# RJ11BMP180_SiHyg.net
KiCad netlist of a schematic drawn in EAGLE
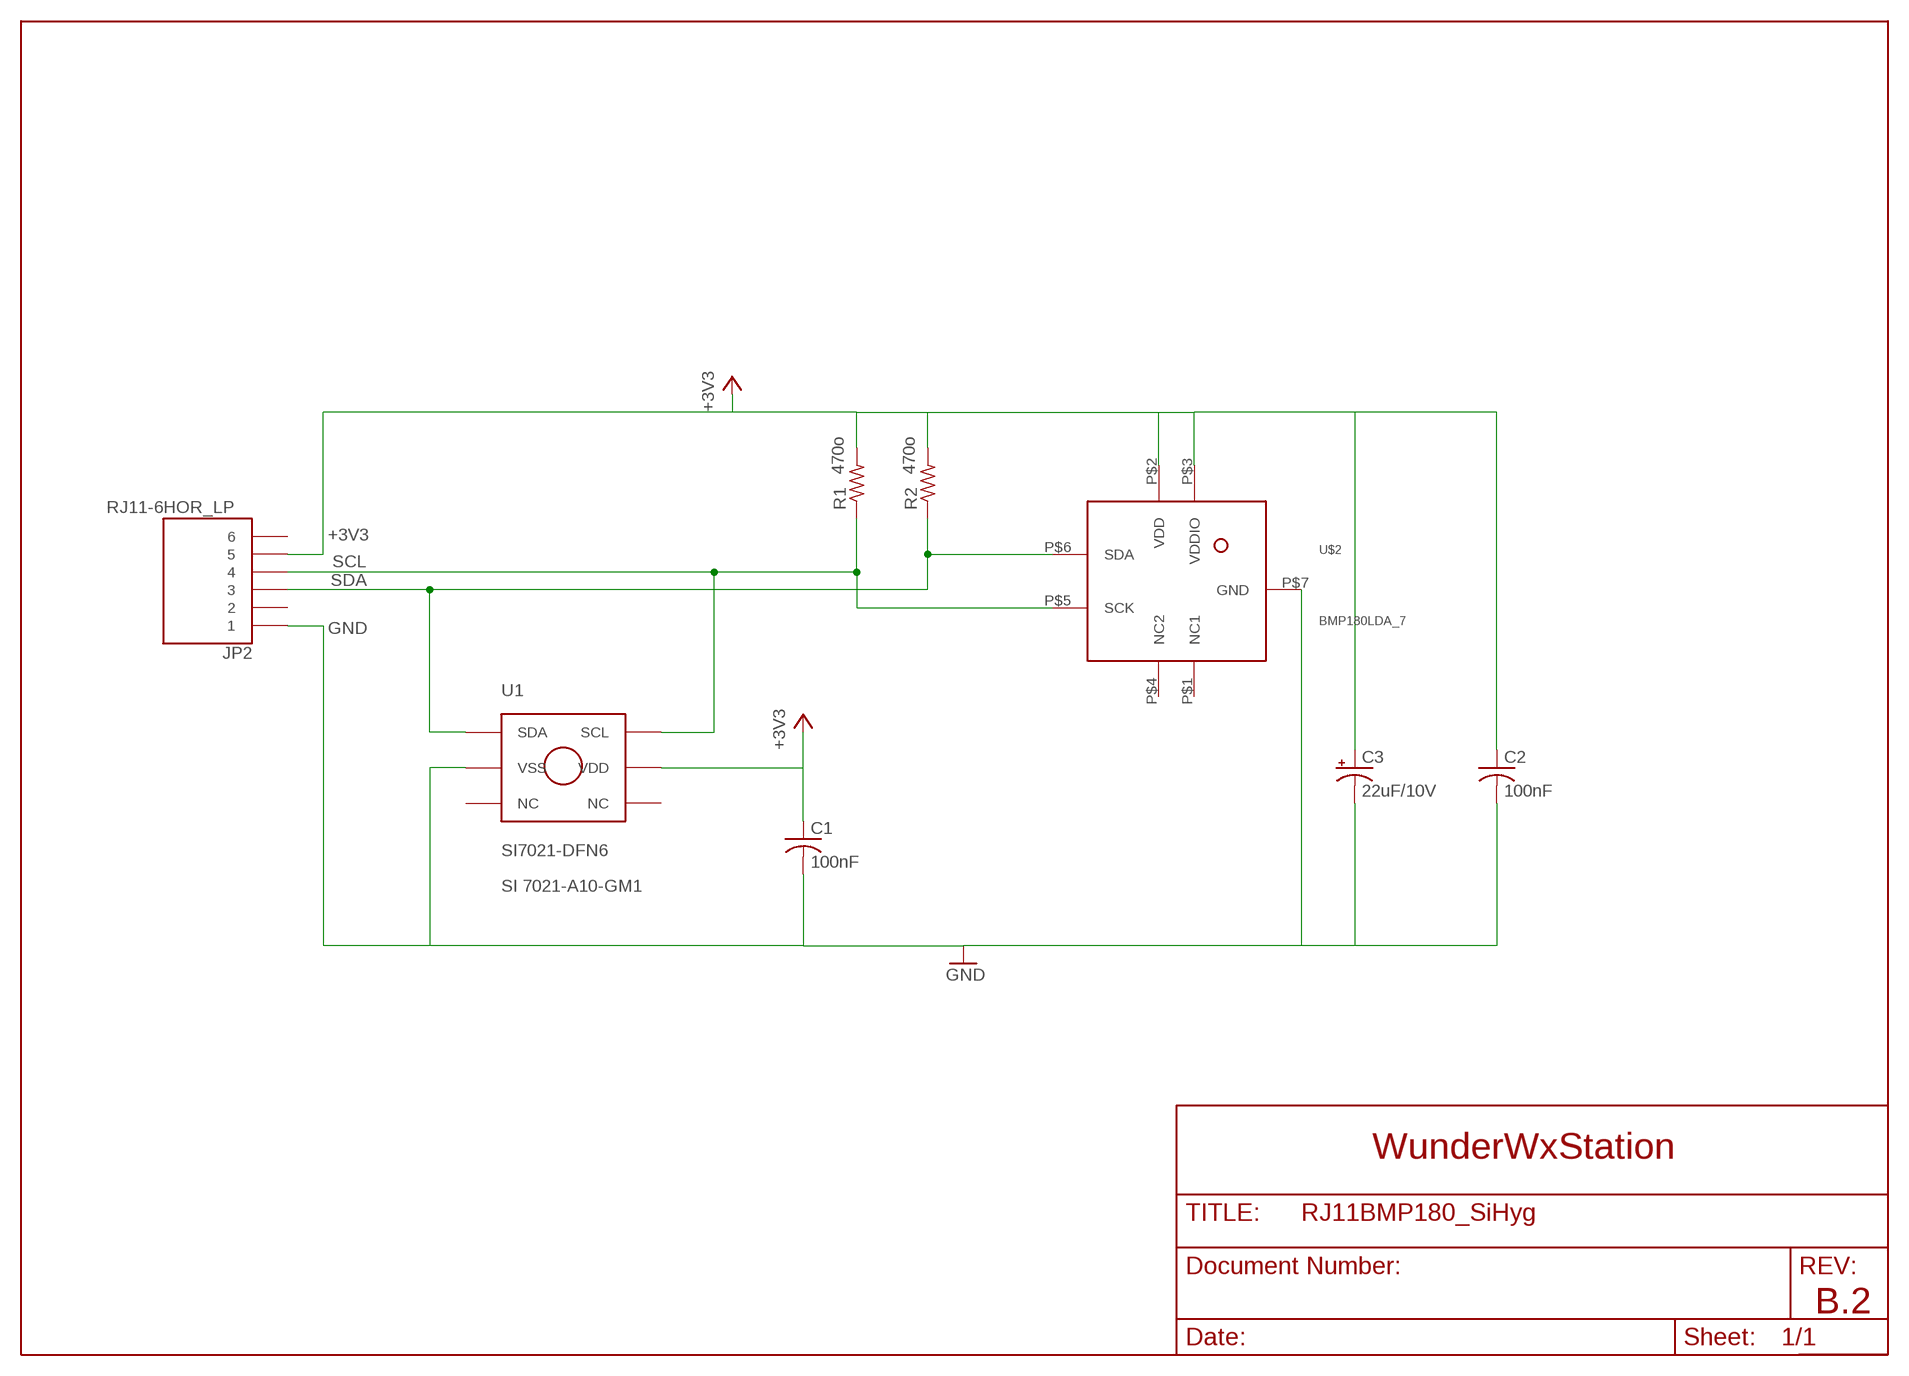
[diagram p0: schematic, sheet 1]

(export (version "E")
  (design (tool "Eeschema 10.0.6"))
  (components
    (comp (ref "C1")
      (value "100nF")
      (footprint "eagle-import:C0805K")
      (libsource (lib "eagle-import") (part "C-USC0805K"))
    )
    (comp (ref "C2")
      (value "100nF")
      (footprint "eagle-import:C0805K")
      (libsource (lib "eagle-import") (part "C-USC0805K"))
    )
    (comp (ref "C3")
      (value "22uF/10V")
      (footprint "eagle-import:SMC_B")
      (libsource (lib "eagle-import") (part "CPOL-USSMCB"))
    )
    (comp (ref "JP2")
      (value "RJ11-6HOR_LP")
      (footprint "eagle-import:RJ11_HOR_LP")
      (libsource (lib "eagle-import") (part "RJ11-6HOR_LP"))
    )
    (comp (ref "R1")
      (value "470o")
      (footprint "eagle-import:R0603")
      (libsource (lib "eagle-import") (part "R-US_R0603"))
    )
    (comp (ref "R2")
      (value "470o")
      (footprint "eagle-import:R0603")
      (libsource (lib "eagle-import") (part "R-US_R0603"))
    )
    (comp (ref "U$2")
      (value "BMP180LDA_7")
      (footprint "eagle-import:LGA_7")
      (libsource (lib "eagle-import") (part "BMP180LDA_7"))
    )
    (comp (ref "U1")
      (value "SI7021-DFN6")
      (footprint "eagle-import:DFN-6_SILABS")
      (libsource (lib "eagle-import") (part "SI7021-DFN6"))
    )
  )
  (nets
    (net (code "1") (name "+3V3") (class "Default")
      (node (ref "C1") (pin "1") (pinfunction "1_1") (pintype "passive"))
      (node (ref "C2") (pin "1") (pinfunction "1_1") (pintype "passive"))
      (node (ref "C3") (pin "+") (pinfunction "+_+") (pintype "passive"))
      (node (ref "JP2") (pin "P$5") (pinfunction "5_P$5") (pintype "bidirectional"))
      (node (ref "R1") (pin "2") (pinfunction "2_2") (pintype "passive"))
      (node (ref "R2") (pin "2") (pinfunction "2_2") (pintype "passive"))
      (node (ref "U$2") (pin "P$2") (pinfunction "VDD_P$2") (pintype "power_in"))
      (node (ref "U$2") (pin "P$3") (pinfunction "VDDIO_P$3") (pintype "power_in"))
      (node (ref "U1") (pin "P$5") (pinfunction "VDD_P$5") (pintype "power_in"))
    )
    (net (code "2") (name "/SCL") (class "Default")
      (node (ref "JP2") (pin "P$4") (pinfunction "4_P$4") (pintype "bidirectional"))
      (node (ref "R1") (pin "1") (pinfunction "1_1") (pintype "passive"))
      (node (ref "U$2") (pin "P$5") (pinfunction "SCK_P$5") (pintype "input"))
      (node (ref "U1") (pin "P$6") (pinfunction "SCL_P$6") (pintype "bidirectional"))
    )
    (net (code "3") (name "/SDA") (class "Default")
      (node (ref "JP2") (pin "P$3") (pinfunction "3_P$3") (pintype "bidirectional"))
      (node (ref "R2") (pin "1") (pinfunction "1_1") (pintype "passive"))
      (node (ref "U$2") (pin "P$6") (pinfunction "SDA_P$6") (pintype "bidirectional"))
      (node (ref "U1") (pin "P$1") (pinfunction "SDA_P$1") (pintype "bidirectional"))
    )
    (net (code "4") (name "GND") (class "Default")
      (node (ref "C1") (pin "2") (pinfunction "2_2") (pintype "passive"))
      (node (ref "C2") (pin "2") (pinfunction "2_2") (pintype "passive"))
      (node (ref "C3") (pin "-") (pinfunction "-_-") (pintype "passive"))
      (node (ref "JP2") (pin "P$1") (pinfunction "1_P$1") (pintype "bidirectional"))
      (node (ref "U$2") (pin "P$7") (pinfunction "GND_P$7") (pintype "power_in"))
      (node (ref "U1") (pin "P$2") (pinfunction "VSS_P$2") (pintype "power_in"))
    )
    (net (code "5") (name "unconnected-(JP2-2-PadP$2)") (class "Default")
      (node (ref "JP2") (pin "P$2") (pinfunction "2_P$2") (pintype "bidirectional"))
    )
    (net (code "6") (name "unconnected-(JP2-6-PadP$6)") (class "Default")
      (node (ref "JP2") (pin "P$6") (pinfunction "6_P$6") (pintype "bidirectional"))
    )
    (net (code "7") (name "unconnected-(U$2-NC1-PadP$1)") (class "Default")
      (node (ref "U$2") (pin "P$1") (pinfunction "NC1_P$1") (pintype "input"))
    )
    (net (code "8") (name "unconnected-(U$2-NC2-PadP$4)") (class "Default")
      (node (ref "U$2") (pin "P$4") (pinfunction "NC2_P$4") (pintype "no_connect"))
    )
    (net (code "9") (name "unconnected-(U1-NC-PadP$3)") (class "Default")
      (node (ref "U1") (pin "P$3") (pinfunction "NC_P$3") (pintype "no_connect"))
    )
    (net (code "10") (name "unconnected-(U1-NC-PadP$4)") (class "Default")
      (node (ref "U1") (pin "P$4") (pinfunction "NC_P$4") (pintype "no_connect"))
    )
  )
)
